# 3-10.net
KiCad netlist of a schematic drawn in Altium Designer
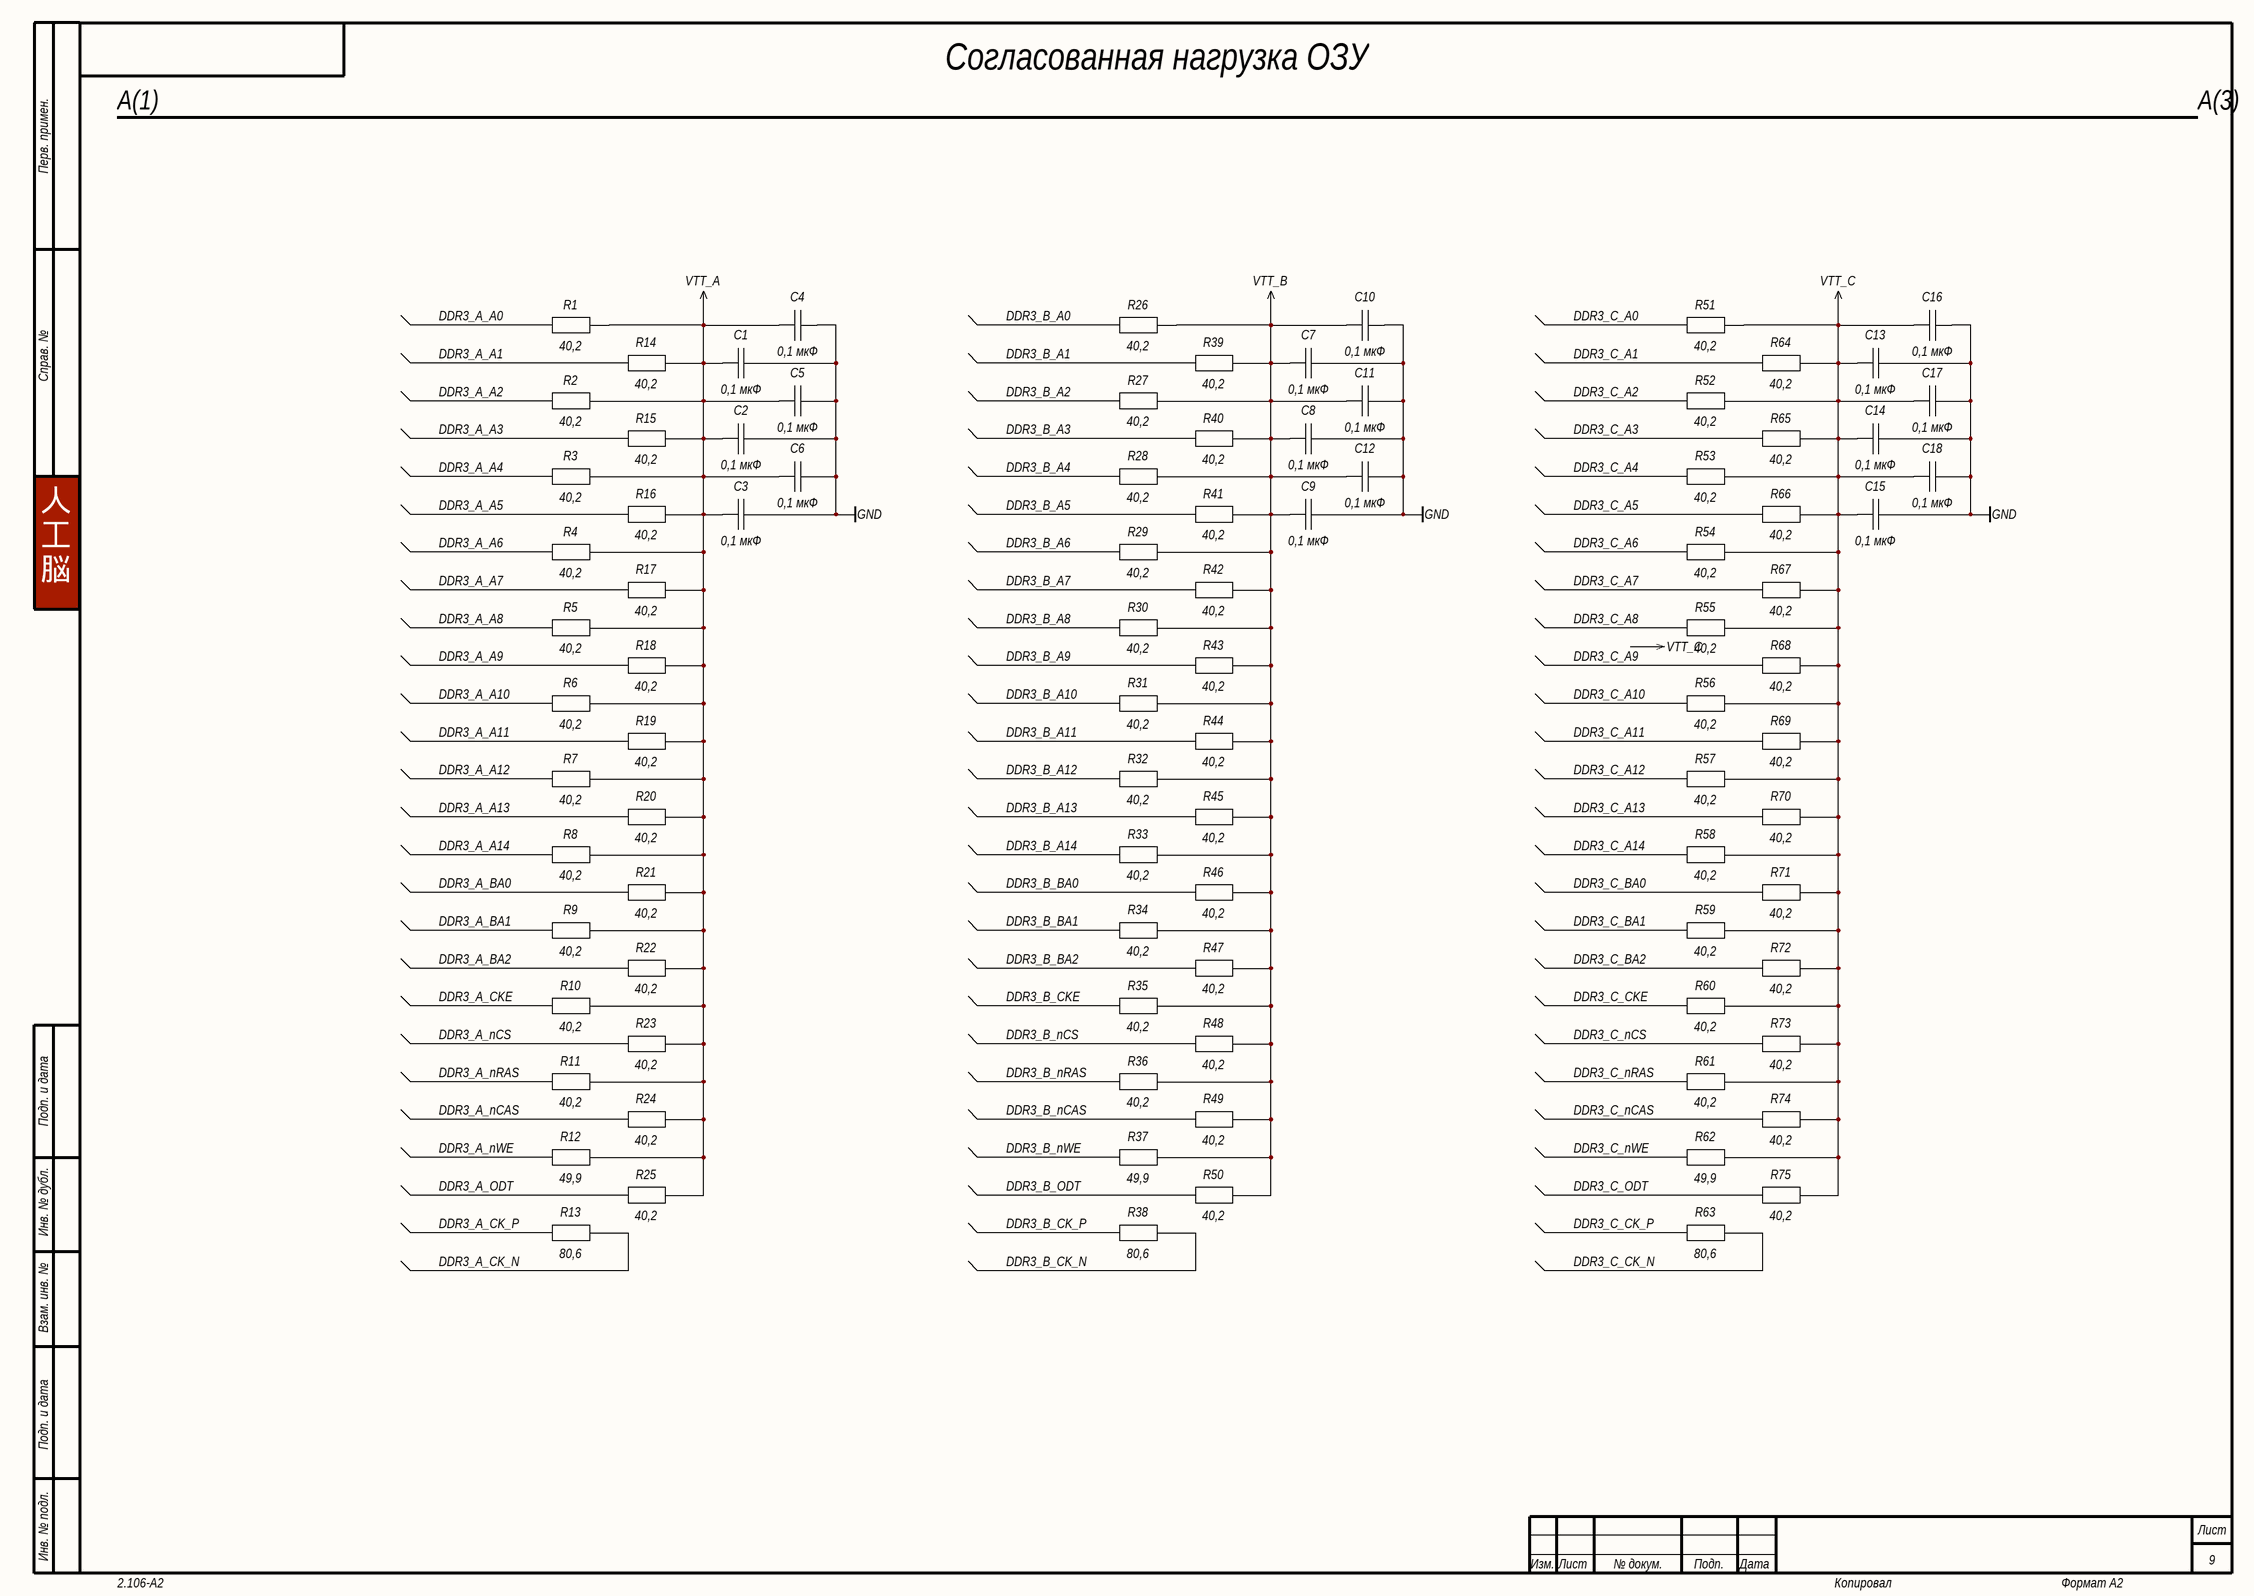
[diagram p0: Э3-10.SchDoc]

(export (version "E")
  (design (tool "Eeschema 10.0.6"))
  (components
    (comp (ref "C1")
      (value "0,1 мкФ")
      (footprint "C0201-B-0.3mm")
      (fields (field (name "Comment") "1"))
      (libsource (lib "Capacitors") (part "Non Polar Hor."))
    )
    (comp (ref "C2")
      (value "0,1 мкФ")
      (footprint "C0201-B-0.3mm")
      (fields (field (name "Comment") "1"))
      (libsource (lib "Capacitors") (part "Non Polar Hor."))
    )
    (comp (ref "C3")
      (value "0,1 мкФ")
      (footprint "C0201-B-0.3mm")
      (fields (field (name "Comment") "1"))
      (libsource (lib "Capacitors") (part "Non Polar Hor."))
    )
    (comp (ref "C4")
      (value "0,1 мкФ")
      (footprint "C0201-B-0.3mm")
      (fields (field (name "Comment") "1"))
      (libsource (lib "Capacitors") (part "Non Polar Hor."))
    )
    (comp (ref "C5")
      (value "0,1 мкФ")
      (footprint "C0201-B-0.3mm")
      (fields (field (name "Comment") "1"))
      (libsource (lib "Capacitors") (part "Non Polar Hor."))
    )
    (comp (ref "C6")
      (value "0,1 мкФ")
      (footprint "C0201-B-0.3mm")
      (fields (field (name "Comment") "1"))
      (libsource (lib "Capacitors") (part "Non Polar Hor."))
    )
    (comp (ref "C7")
      (value "0,1 мкФ")
      (footprint "C0201-B-0.3mm")
      (fields (field (name "Comment") "1"))
      (libsource (lib "Capacitors") (part "Non Polar Hor."))
    )
    (comp (ref "C8")
      (value "0,1 мкФ")
      (footprint "C0201-B-0.3mm")
      (fields (field (name "Comment") "1"))
      (libsource (lib "Capacitors") (part "Non Polar Hor."))
    )
    (comp (ref "C9")
      (value "0,1 мкФ")
      (footprint "C0201-B-0.3mm")
      (fields (field (name "Comment") "1"))
      (libsource (lib "Capacitors") (part "Non Polar Hor."))
    )
    (comp (ref "C10")
      (value "0,1 мкФ")
      (footprint "C0201-B-0.3mm")
      (fields (field (name "Comment") "1"))
      (libsource (lib "Capacitors") (part "Non Polar Hor."))
    )
    (comp (ref "C11")
      (value "0,1 мкФ")
      (footprint "C0201-B-0.3mm")
      (fields (field (name "Comment") "1"))
      (libsource (lib "Capacitors") (part "Non Polar Hor."))
    )
    (comp (ref "C12")
      (value "0,1 мкФ")
      (footprint "C0201-B-0.3mm")
      (fields (field (name "Comment") "1"))
      (libsource (lib "Capacitors") (part "Non Polar Hor."))
    )
    (comp (ref "C13")
      (value "0,1 мкФ")
      (footprint "C0201-B-0.3mm")
      (fields (field (name "Comment") "1"))
      (libsource (lib "Capacitors") (part "Non Polar Hor."))
    )
    (comp (ref "C14")
      (value "0,1 мкФ")
      (footprint "C0201-B-0.3mm")
      (fields (field (name "Comment") "1"))
      (libsource (lib "Capacitors") (part "Non Polar Hor."))
    )
    (comp (ref "C15")
      (value "0,1 мкФ")
      (footprint "C0201-B-0.3mm")
      (fields (field (name "Comment") "1"))
      (libsource (lib "Capacitors") (part "Non Polar Hor."))
    )
    (comp (ref "C16")
      (value "0,1 мкФ")
      (footprint "C0201-B-0.3mm")
      (fields (field (name "Comment") "1"))
      (libsource (lib "Capacitors") (part "Non Polar Hor."))
    )
    (comp (ref "C17")
      (value "0,1 мкФ")
      (footprint "C0201-B-0.3mm")
      (fields (field (name "Comment") "1"))
      (libsource (lib "Capacitors") (part "Non Polar Hor."))
    )
    (comp (ref "C18")
      (value "0,1 мкФ")
      (footprint "C0201-B-0.3mm")
      (fields (field (name "Comment") "1"))
      (libsource (lib "Capacitors") (part "Non Polar Hor."))
    )
    (comp (ref "R1")
      (value "40,2")
      (footprint "CR0201-B-0.25mm")
      (fields (field (name "Comment") "1"))
      (libsource (lib "Resistors") (part "Resistor Hor."))
    )
    (comp (ref "R2")
      (value "40,2")
      (footprint "CR0201-B-0.25mm")
      (fields (field (name "Comment") "1"))
      (libsource (lib "Resistors") (part "Resistor Hor."))
    )
    (comp (ref "R3")
      (value "40,2")
      (footprint "CR0201-B-0.25mm")
      (fields (field (name "Comment") "1"))
      (libsource (lib "Resistors") (part "Resistor Hor."))
    )
    (comp (ref "R4")
      (value "40,2")
      (footprint "CR0201-B-0.25mm")
      (fields (field (name "Comment") "1"))
      (libsource (lib "Resistors") (part "Resistor Hor."))
    )
    (comp (ref "R5")
      (value "40,2")
      (footprint "CR0201-B-0.25mm")
      (fields (field (name "Comment") "1"))
      (libsource (lib "Resistors") (part "Resistor Hor."))
    )
    (comp (ref "R6")
      (value "40,2")
      (footprint "CR0201-B-0.25mm")
      (fields (field (name "Comment") "1"))
      (libsource (lib "Resistors") (part "Resistor Hor."))
    )
    (comp (ref "R7")
      (value "40,2")
      (footprint "CR0201-B-0.25mm")
      (fields (field (name "Comment") "1"))
      (libsource (lib "Resistors") (part "Resistor Hor."))
    )
    (comp (ref "R8")
      (value "40,2")
      (footprint "CR0201-B-0.25mm")
      (fields (field (name "Comment") "1"))
      (libsource (lib "Resistors") (part "Resistor Hor."))
    )
    (comp (ref "R9")
      (value "40,2")
      (footprint "CR0201-B-0.25mm")
      (fields (field (name "Comment") "1"))
      (libsource (lib "Resistors") (part "Resistor Hor."))
    )
    (comp (ref "R10")
      (value "40,2")
      (footprint "CR0201-B-0.25mm")
      (fields (field (name "Comment") "1"))
      (libsource (lib "Resistors") (part "Resistor Hor."))
    )
    (comp (ref "R11")
      (value "40,2")
      (footprint "CR0201-B-0.25mm")
      (fields (field (name "Comment") "1"))
      (libsource (lib "Resistors") (part "Resistor Hor."))
    )
    (comp (ref "R12")
      (value "49,9")
      (footprint "CR0201-B-0.25mm")
      (fields (field (name "Comment") "1"))
      (libsource (lib "Resistors") (part "Resistor Hor."))
    )
    (comp (ref "R13")
      (value "80,6")
      (footprint "CR0201-B-0.25mm")
      (fields (field (name "Comment") "1"))
      (libsource (lib "Resistors") (part "Resistor Hor."))
    )
    (comp (ref "R14")
      (value "40,2")
      (footprint "CR0201-B-0.25mm")
      (fields (field (name "Comment") "1"))
      (libsource (lib "Resistors") (part "Resistor Hor."))
    )
    (comp (ref "R15")
      (value "40,2")
      (footprint "CR0201-B-0.25mm")
      (fields (field (name "Comment") "1"))
      (libsource (lib "Resistors") (part "Resistor Hor."))
    )
    (comp (ref "R16")
      (value "40,2")
      (footprint "CR0201-B-0.25mm")
      (fields (field (name "Comment") "1"))
      (libsource (lib "Resistors") (part "Resistor Hor."))
    )
    (comp (ref "R17")
      (value "40,2")
      (footprint "CR0201-B-0.25mm")
      (fields (field (name "Comment") "1"))
      (libsource (lib "Resistors") (part "Resistor Hor."))
    )
    (comp (ref "R18")
      (value "40,2")
      (footprint "CR0201-B-0.25mm")
      (fields (field (name "Comment") "1"))
      (libsource (lib "Resistors") (part "Resistor Hor."))
    )
    (comp (ref "R19")
      (value "40,2")
      (footprint "CR0201-B-0.25mm")
      (fields (field (name "Comment") "1"))
      (libsource (lib "Resistors") (part "Resistor Hor."))
    )
    (comp (ref "R20")
      (value "40,2")
      (footprint "CR0201-B-0.25mm")
      (fields (field (name "Comment") "1"))
      (libsource (lib "Resistors") (part "Resistor Hor."))
    )
    (comp (ref "R21")
      (value "40,2")
      (footprint "CR0201-B-0.25mm")
      (fields (field (name "Comment") "1"))
      (libsource (lib "Resistors") (part "Resistor Hor."))
    )
    (comp (ref "R22")
      (value "40,2")
      (footprint "CR0201-B-0.25mm")
      (fields (field (name "Comment") "1"))
      (libsource (lib "Resistors") (part "Resistor Hor."))
    )
    (comp (ref "R23")
      (value "40,2")
      (footprint "CR0201-B-0.25mm")
      (fields (field (name "Comment") "1"))
      (libsource (lib "Resistors") (part "Resistor Hor."))
    )
    (comp (ref "R24")
      (value "40,2")
      (footprint "CR0201-B-0.25mm")
      (fields (field (name "Comment") "1"))
      (libsource (lib "Resistors") (part "Resistor Hor."))
    )
    (comp (ref "R25")
      (value "40,2")
      (footprint "CR0201-B-0.25mm")
      (fields (field (name "Comment") "1"))
      (libsource (lib "Resistors") (part "Resistor Hor."))
    )
    (comp (ref "R26")
      (value "40,2")
      (footprint "CR0201-B-0.25mm")
      (fields (field (name "Comment") "1"))
      (libsource (lib "Resistors") (part "Resistor Hor."))
    )
    (comp (ref "R27")
      (value "40,2")
      (footprint "CR0201-B-0.25mm")
      (fields (field (name "Comment") "1"))
      (libsource (lib "Resistors") (part "Resistor Hor."))
    )
    (comp (ref "R28")
      (value "40,2")
      (footprint "CR0201-B-0.25mm")
      (fields (field (name "Comment") "1"))
      (libsource (lib "Resistors") (part "Resistor Hor."))
    )
    (comp (ref "R29")
      (value "40,2")
      (footprint "CR0201-B-0.25mm")
      (fields (field (name "Comment") "1"))
      (libsource (lib "Resistors") (part "Resistor Hor."))
    )
    (comp (ref "R30")
      (value "40,2")
      (footprint "CR0201-B-0.25mm")
      (fields (field (name "Comment") "1"))
      (libsource (lib "Resistors") (part "Resistor Hor."))
    )
    (comp (ref "R31")
      (value "40,2")
      (footprint "CR0201-B-0.25mm")
      (fields (field (name "Comment") "1"))
      (libsource (lib "Resistors") (part "Resistor Hor."))
    )
    (comp (ref "R32")
      (value "40,2")
      (footprint "CR0201-B-0.25mm")
      (fields (field (name "Comment") "1"))
      (libsource (lib "Resistors") (part "Resistor Hor."))
    )
    (comp (ref "R33")
      (value "40,2")
      (footprint "CR0201-B-0.25mm")
      (fields (field (name "Comment") "1"))
      (libsource (lib "Resistors") (part "Resistor Hor."))
    )
    (comp (ref "R34")
      (value "40,2")
      (footprint "CR0201-B-0.25mm")
      (fields (field (name "Comment") "1"))
      (libsource (lib "Resistors") (part "Resistor Hor."))
    )
    (comp (ref "R35")
      (value "40,2")
      (footprint "CR0201-B-0.25mm")
      (fields (field (name "Comment") "1"))
      (libsource (lib "Resistors") (part "Resistor Hor."))
    )
    (comp (ref "R36")
      (value "40,2")
      (footprint "CR0201-B-0.25mm")
      (fields (field (name "Comment") "1"))
      (libsource (lib "Resistors") (part "Resistor Hor."))
    )
    (comp (ref "R37")
      (value "49,9")
      (footprint "CR0201-B-0.25mm")
      (fields (field (name "Comment") "1"))
      (libsource (lib "Resistors") (part "Resistor Hor."))
    )
    (comp (ref "R38")
      (value "80,6")
      (footprint "CR0201-B-0.25mm")
      (fields (field (name "Comment") "1"))
      (libsource (lib "Resistors") (part "Resistor Hor."))
    )
    (comp (ref "R39")
      (value "40,2")
      (footprint "CR0201-B-0.25mm")
      (fields (field (name "Comment") "1"))
      (libsource (lib "Resistors") (part "Resistor Hor."))
    )
    (comp (ref "R40")
      (value "40,2")
      (footprint "CR0201-B-0.25mm")
      (fields (field (name "Comment") "1"))
      (libsource (lib "Resistors") (part "Resistor Hor."))
    )
    (comp (ref "R41")
      (value "40,2")
      (footprint "CR0201-B-0.25mm")
      (fields (field (name "Comment") "1"))
      (libsource (lib "Resistors") (part "Resistor Hor."))
    )
    (comp (ref "R42")
      (value "40,2")
      (footprint "CR0201-B-0.25mm")
      (fields (field (name "Comment") "1"))
      (libsource (lib "Resistors") (part "Resistor Hor."))
    )
    (comp (ref "R43")
      (value "40,2")
      (footprint "CR0201-B-0.25mm")
      (fields (field (name "Comment") "1"))
      (libsource (lib "Resistors") (part "Resistor Hor."))
    )
    (comp (ref "R44")
      (value "40,2")
      (footprint "CR0201-B-0.25mm")
      (fields (field (name "Comment") "1"))
      (libsource (lib "Resistors") (part "Resistor Hor."))
    )
    (comp (ref "R45")
      (value "40,2")
      (footprint "CR0201-B-0.25mm")
      (fields (field (name "Comment") "1"))
      (libsource (lib "Resistors") (part "Resistor Hor."))
    )
    (comp (ref "R46")
      (value "40,2")
      (footprint "CR0201-B-0.25mm")
      (fields (field (name "Comment") "1"))
      (libsource (lib "Resistors") (part "Resistor Hor."))
    )
    (comp (ref "R47")
      (value "40,2")
      (footprint "CR0201-B-0.25mm")
      (fields (field (name "Comment") "1"))
      (libsource (lib "Resistors") (part "Resistor Hor."))
    )
    (comp (ref "R48")
      (value "40,2")
      (footprint "CR0201-B-0.25mm")
      (fields (field (name "Comment") "1"))
      (libsource (lib "Resistors") (part "Resistor Hor."))
    )
    (comp (ref "R49")
      (value "40,2")
      (footprint "CR0201-B-0.25mm")
      (fields (field (name "Comment") "1"))
      (libsource (lib "Resistors") (part "Resistor Hor."))
    )
    (comp (ref "R50")
      (value "40,2")
      (footprint "CR0201-B-0.25mm")
      (fields (field (name "Comment") "1"))
      (libsource (lib "Resistors") (part "Resistor Hor."))
    )
    (comp (ref "R51")
      (value "40,2")
      (footprint "CR0201-B-0.25mm")
      (fields (field (name "Comment") "1"))
      (libsource (lib "Resistors") (part "Resistor Hor."))
    )
    (comp (ref "R52")
      (value "40,2")
      (footprint "CR0201-B-0.25mm")
      (fields (field (name "Comment") "1"))
      (libsource (lib "Resistors") (part "Resistor Hor."))
    )
    (comp (ref "R53")
      (value "40,2")
      (footprint "CR0201-B-0.25mm")
      (fields (field (name "Comment") "1"))
      (libsource (lib "Resistors") (part "Resistor Hor."))
    )
    (comp (ref "R54")
      (value "40,2")
      (footprint "CR0201-B-0.25mm")
      (fields (field (name "Comment") "1"))
      (libsource (lib "Resistors") (part "Resistor Hor."))
    )
    (comp (ref "R55")
      (value "40,2")
      (footprint "CR0201-B-0.25mm")
      (fields (field (name "Comment") "1"))
      (libsource (lib "Resistors") (part "Resistor Hor."))
    )
    (comp (ref "R56")
      (value "40,2")
      (footprint "CR0201-B-0.25mm")
      (fields (field (name "Comment") "1"))
      (libsource (lib "Resistors") (part "Resistor Hor."))
    )
    (comp (ref "R57")
      (value "40,2")
      (footprint "CR0201-B-0.25mm")
      (fields (field (name "Comment") "1"))
      (libsource (lib "Resistors") (part "Resistor Hor."))
    )
    (comp (ref "R58")
      (value "40,2")
      (footprint "CR0201-B-0.25mm")
      (fields (field (name "Comment") "1"))
      (libsource (lib "Resistors") (part "Resistor Hor."))
    )
    (comp (ref "R59")
      (value "40,2")
      (footprint "CR0201-B-0.25mm")
      (fields (field (name "Comment") "1"))
      (libsource (lib "Resistors") (part "Resistor Hor."))
    )
    (comp (ref "R60")
      (value "40,2")
      (footprint "CR0201-B-0.25mm")
      (fields (field (name "Comment") "1"))
      (libsource (lib "Resistors") (part "Resistor Hor."))
    )
    (comp (ref "R61")
      (value "40,2")
      (footprint "CR0201-B-0.25mm")
      (fields (field (name "Comment") "1"))
      (libsource (lib "Resistors") (part "Resistor Hor."))
    )
    (comp (ref "R62")
      (value "49,9")
      (footprint "CR0201-B-0.25mm")
      (fields (field (name "Comment") "1"))
      (libsource (lib "Resistors") (part "Resistor Hor."))
    )
    (comp (ref "R63")
      (value "80,6")
      (footprint "CR0201-B-0.25mm")
      (fields (field (name "Comment") "1"))
      (libsource (lib "Resistors") (part "Resistor Hor."))
    )
    (comp (ref "R64")
      (value "40,2")
      (footprint "CR0201-B-0.25mm")
      (fields (field (name "Comment") "1"))
      (libsource (lib "Resistors") (part "Resistor Hor."))
    )
    (comp (ref "R65")
      (value "40,2")
      (footprint "CR0201-B-0.25mm")
      (fields (field (name "Comment") "1"))
      (libsource (lib "Resistors") (part "Resistor Hor."))
    )
    (comp (ref "R66")
      (value "40,2")
      (footprint "CR0201-B-0.25mm")
      (fields (field (name "Comment") "1"))
      (libsource (lib "Resistors") (part "Resistor Hor."))
    )
    (comp (ref "R67")
      (value "40,2")
      (footprint "CR0201-B-0.25mm")
      (fields (field (name "Comment") "1"))
      (libsource (lib "Resistors") (part "Resistor Hor."))
    )
    (comp (ref "R68")
      (value "40,2")
      (footprint "CR0201-B-0.25mm")
      (fields (field (name "Comment") "1"))
      (libsource (lib "Resistors") (part "Resistor Hor."))
    )
    (comp (ref "R69")
      (value "40,2")
      (footprint "CR0201-B-0.25mm")
      (fields (field (name "Comment") "1"))
      (libsource (lib "Resistors") (part "Resistor Hor."))
    )
    (comp (ref "R70")
      (value "40,2")
      (footprint "CR0201-B-0.25mm")
      (fields (field (name "Comment") "1"))
      (libsource (lib "Resistors") (part "Resistor Hor."))
    )
    (comp (ref "R71")
      (value "40,2")
      (footprint "CR0201-B-0.25mm")
      (fields (field (name "Comment") "1"))
      (libsource (lib "Resistors") (part "Resistor Hor."))
    )
    (comp (ref "R72")
      (value "40,2")
      (footprint "CR0201-B-0.25mm")
      (fields (field (name "Comment") "1"))
      (libsource (lib "Resistors") (part "Resistor Hor."))
    )
    (comp (ref "R73")
      (value "40,2")
      (footprint "CR0201-B-0.25mm")
      (fields (field (name "Comment") "1"))
      (libsource (lib "Resistors") (part "Resistor Hor."))
    )
    (comp (ref "R74")
      (value "40,2")
      (footprint "CR0201-B-0.25mm")
      (fields (field (name "Comment") "1"))
      (libsource (lib "Resistors") (part "Resistor Hor."))
    )
    (comp (ref "R75")
      (value "40,2")
      (footprint "CR0201-B-0.25mm")
      (fields (field (name "Comment") "1"))
      (libsource (lib "Resistors") (part "Resistor Hor."))
    )
  )
  (nets
    (net (code "1") (name "/DDR3_A_A0") (class "Default")
      (node (ref "R1") (pin "1") (pinfunction "1_1") (pintype "passive"))
    )
    (net (code "2") (name "/DDR3_A_A1") (class "Default")
      (node (ref "R14") (pin "1") (pinfunction "1_1") (pintype "passive"))
    )
    (net (code "3") (name "/DDR3_A_A2") (class "Default")
      (node (ref "R2") (pin "1") (pinfunction "1_1") (pintype "passive"))
    )
    (net (code "4") (name "/DDR3_A_A3") (class "Default")
      (node (ref "R15") (pin "1") (pinfunction "1_1") (pintype "passive"))
    )
    (net (code "5") (name "/DDR3_A_A4") (class "Default")
      (node (ref "R3") (pin "1") (pinfunction "1_1") (pintype "passive"))
    )
    (net (code "6") (name "/DDR3_A_A5") (class "Default")
      (node (ref "R16") (pin "1") (pinfunction "1_1") (pintype "passive"))
    )
    (net (code "7") (name "/DDR3_A_A6") (class "Default")
      (node (ref "R4") (pin "1") (pinfunction "1_1") (pintype "passive"))
    )
    (net (code "8") (name "/DDR3_A_A7") (class "Default")
      (node (ref "R17") (pin "1") (pinfunction "1_1") (pintype "passive"))
    )
    (net (code "9") (name "/DDR3_A_A8") (class "Default")
      (node (ref "R5") (pin "1") (pinfunction "1_1") (pintype "passive"))
    )
    (net (code "10") (name "/DDR3_A_A9") (class "Default")
      (node (ref "R18") (pin "1") (pinfunction "1_1") (pintype "passive"))
    )
    (net (code "11") (name "/DDR3_A_A10") (class "Default")
      (node (ref "R6") (pin "1") (pinfunction "1_1") (pintype "passive"))
    )
    (net (code "12") (name "/DDR3_A_A11") (class "Default")
      (node (ref "R19") (pin "1") (pinfunction "1_1") (pintype "passive"))
    )
    (net (code "13") (name "/DDR3_A_A12") (class "Default")
      (node (ref "R7") (pin "1") (pinfunction "1_1") (pintype "passive"))
    )
    (net (code "14") (name "/DDR3_A_A13") (class "Default")
      (node (ref "R20") (pin "1") (pinfunction "1_1") (pintype "passive"))
    )
    (net (code "15") (name "/DDR3_A_A14") (class "Default")
      (node (ref "R8") (pin "1") (pinfunction "1_1") (pintype "passive"))
    )
    (net (code "16") (name "/DDR3_A_BA0") (class "Default")
      (node (ref "R21") (pin "1") (pinfunction "1_1") (pintype "passive"))
    )
    (net (code "17") (name "/DDR3_A_BA1") (class "Default")
      (node (ref "R9") (pin "1") (pinfunction "1_1") (pintype "passive"))
    )
    (net (code "18") (name "/DDR3_A_BA2") (class "Default")
      (node (ref "R22") (pin "1") (pinfunction "1_1") (pintype "passive"))
    )
    (net (code "19") (name "/DDR3_A_CKE") (class "Default")
      (node (ref "R10") (pin "1") (pinfunction "1_1") (pintype "passive"))
    )
    (net (code "20") (name "/DDR3_A_CK_N") (class "Default")
      (node (ref "R13") (pin "2") (pinfunction "2_2") (pintype "passive"))
    )
    (net (code "21") (name "/DDR3_A_CK_P") (class "Default")
      (node (ref "R13") (pin "1") (pinfunction "1_1") (pintype "passive"))
    )
    (net (code "22") (name "/DDR3_A_ODT") (class "Default")
      (node (ref "R25") (pin "1") (pinfunction "1_1") (pintype "passive"))
    )
    (net (code "23") (name "/DDR3_A_nCAS") (class "Default")
      (node (ref "R24") (pin "1") (pinfunction "1_1") (pintype "passive"))
    )
    (net (code "24") (name "/DDR3_A_nCS") (class "Default")
      (node (ref "R23") (pin "1") (pinfunction "1_1") (pintype "passive"))
    )
    (net (code "25") (name "/DDR3_A_nRAS") (class "Default")
      (node (ref "R11") (pin "1") (pinfunction "1_1") (pintype "passive"))
    )
    (net (code "26") (name "/DDR3_A_nWE") (class "Default")
      (node (ref "R12") (pin "1") (pinfunction "1_1") (pintype "passive"))
    )
    (net (code "27") (name "/DDR3_B_A0") (class "Default")
      (node (ref "R26") (pin "1") (pinfunction "1_1") (pintype "passive"))
    )
    (net (code "28") (name "/DDR3_B_A1") (class "Default")
      (node (ref "R39") (pin "1") (pinfunction "1_1") (pintype "passive"))
    )
    (net (code "29") (name "/DDR3_B_A2") (class "Default")
      (node (ref "R27") (pin "1") (pinfunction "1_1") (pintype "passive"))
    )
    (net (code "30") (name "/DDR3_B_A3") (class "Default")
      (node (ref "R40") (pin "1") (pinfunction "1_1") (pintype "passive"))
    )
    (net (code "31") (name "/DDR3_B_A4") (class "Default")
      (node (ref "R28") (pin "1") (pinfunction "1_1") (pintype "passive"))
    )
    (net (code "32") (name "/DDR3_B_A5") (class "Default")
      (node (ref "R41") (pin "1") (pinfunction "1_1") (pintype "passive"))
    )
    (net (code "33") (name "/DDR3_B_A6") (class "Default")
      (node (ref "R29") (pin "1") (pinfunction "1_1") (pintype "passive"))
    )
    (net (code "34") (name "/DDR3_B_A7") (class "Default")
      (node (ref "R42") (pin "1") (pinfunction "1_1") (pintype "passive"))
    )
    (net (code "35") (name "/DDR3_B_A8") (class "Default")
      (node (ref "R30") (pin "1") (pinfunction "1_1") (pintype "passive"))
    )
    (net (code "36") (name "/DDR3_B_A9") (class "Default")
      (node (ref "R43") (pin "1") (pinfunction "1_1") (pintype "passive"))
    )
    (net (code "37") (name "/DDR3_B_A10") (class "Default")
      (node (ref "R31") (pin "1") (pinfunction "1_1") (pintype "passive"))
    )
    (net (code "38") (name "/DDR3_B_A11") (class "Default")
      (node (ref "R44") (pin "1") (pinfunction "1_1") (pintype "passive"))
    )
    (net (code "39") (name "/DDR3_B_A12") (class "Default")
      (node (ref "R32") (pin "1") (pinfunction "1_1") (pintype "passive"))
    )
    (net (code "40") (name "/DDR3_B_A13") (class "Default")
      (node (ref "R45") (pin "1") (pinfunction "1_1") (pintype "passive"))
    )
    (net (code "41") (name "/DDR3_B_A14") (class "Default")
      (node (ref "R33") (pin "1") (pinfunction "1_1") (pintype "passive"))
    )
    (net (code "42") (name "/DDR3_B_BA0") (class "Default")
      (node (ref "R46") (pin "1") (pinfunction "1_1") (pintype "passive"))
    )
    (net (code "43") (name "/DDR3_B_BA1") (class "Default")
      (node (ref "R34") (pin "1") (pinfunction "1_1") (pintype "passive"))
    )
    (net (code "44") (name "/DDR3_B_BA2") (class "Default")
      (node (ref "R47") (pin "1") (pinfunction "1_1") (pintype "passive"))
    )
    (net (code "45") (name "/DDR3_B_CKE") (class "Default")
      (node (ref "R35") (pin "1") (pinfunction "1_1") (pintype "passive"))
    )
    (net (code "46") (name "/DDR3_B_CK_N") (class "Default")
      (node (ref "R38") (pin "2") (pinfunction "2_2") (pintype "passive"))
    )
    (net (code "47") (name "/DDR3_B_CK_P") (class "Default")
      (node (ref "R38") (pin "1") (pinfunction "1_1") (pintype "passive"))
    )
    (net (code "48") (name "/DDR3_B_ODT") (class "Default")
      (node (ref "R50") (pin "1") (pinfunction "1_1") (pintype "passive"))
    )
    (net (code "49") (name "/DDR3_B_nCAS") (class "Default")
      (node (ref "R49") (pin "1") (pinfunction "1_1") (pintype "passive"))
    )
    (net (code "50") (name "/DDR3_B_nCS") (class "Default")
      (node (ref "R48") (pin "1") (pinfunction "1_1") (pintype "passive"))
    )
    (net (code "51") (name "/DDR3_B_nRAS") (class "Default")
      (node (ref "R36") (pin "1") (pinfunction "1_1") (pintype "passive"))
    )
    (net (code "52") (name "/DDR3_B_nWE") (class "Default")
      (node (ref "R37") (pin "1") (pinfunction "1_1") (pintype "passive"))
    )
    (net (code "53") (name "/DDR3_C_A0") (class "Default")
      (node (ref "R51") (pin "1") (pinfunction "1_1") (pintype "passive"))
    )
    (net (code "54") (name "/DDR3_C_A1") (class "Default")
      (node (ref "R64") (pin "1") (pinfunction "1_1") (pintype "passive"))
    )
    (net (code "55") (name "/DDR3_C_A2") (class "Default")
      (node (ref "R52") (pin "1") (pinfunction "1_1") (pintype "passive"))
    )
    (net (code "56") (name "/DDR3_C_A3") (class "Default")
      (node (ref "R65") (pin "1") (pinfunction "1_1") (pintype "passive"))
    )
    (net (code "57") (name "/DDR3_C_A4") (class "Default")
      (node (ref "R53") (pin "1") (pinfunction "1_1") (pintype "passive"))
    )
    (net (code "58") (name "/DDR3_C_A5") (class "Default")
      (node (ref "R66") (pin "1") (pinfunction "1_1") (pintype "passive"))
    )
    (net (code "59") (name "/DDR3_C_A6") (class "Default")
      (node (ref "R54") (pin "1") (pinfunction "1_1") (pintype "passive"))
    )
    (net (code "60") (name "/DDR3_C_A7") (class "Default")
      (node (ref "R67") (pin "1") (pinfunction "1_1") (pintype "passive"))
    )
    (net (code "61") (name "/DDR3_C_A8") (class "Default")
      (node (ref "R55") (pin "1") (pinfunction "1_1") (pintype "passive"))
    )
    (net (code "62") (name "/DDR3_C_A9") (class "Default")
      (node (ref "R68") (pin "1") (pinfunction "1_1") (pintype "passive"))
    )
    (net (code "63") (name "/DDR3_C_A10") (class "Default")
      (node (ref "R56") (pin "1") (pinfunction "1_1") (pintype "passive"))
    )
    (net (code "64") (name "/DDR3_C_A11") (class "Default")
      (node (ref "R69") (pin "1") (pinfunction "1_1") (pintype "passive"))
    )
    (net (code "65") (name "/DDR3_C_A12") (class "Default")
      (node (ref "R57") (pin "1") (pinfunction "1_1") (pintype "passive"))
    )
    (net (code "66") (name "/DDR3_C_A13") (class "Default")
      (node (ref "R70") (pin "1") (pinfunction "1_1") (pintype "passive"))
    )
    (net (code "67") (name "/DDR3_C_A14") (class "Default")
      (node (ref "R58") (pin "1") (pinfunction "1_1") (pintype "passive"))
    )
    (net (code "68") (name "/DDR3_C_BA0") (class "Default")
      (node (ref "R71") (pin "1") (pinfunction "1_1") (pintype "passive"))
    )
    (net (code "69") (name "/DDR3_C_BA1") (class "Default")
      (node (ref "R59") (pin "1") (pinfunction "1_1") (pintype "passive"))
    )
    (net (code "70") (name "/DDR3_C_BA2") (class "Default")
      (node (ref "R72") (pin "1") (pinfunction "1_1") (pintype "passive"))
    )
    (net (code "71") (name "/DDR3_C_CKE") (class "Default")
      (node (ref "R60") (pin "1") (pinfunction "1_1") (pintype "passive"))
    )
    (net (code "72") (name "/DDR3_C_CK_N") (class "Default")
      (node (ref "R63") (pin "2") (pinfunction "2_2") (pintype "passive"))
    )
    (net (code "73") (name "/DDR3_C_CK_P") (class "Default")
      (node (ref "R63") (pin "1") (pinfunction "1_1") (pintype "passive"))
    )
    (net (code "74") (name "/DDR3_C_ODT") (class "Default")
      (node (ref "R75") (pin "1") (pinfunction "1_1") (pintype "passive"))
    )
    (net (code "75") (name "/DDR3_C_nCAS") (class "Default")
      (node (ref "R74") (pin "1") (pinfunction "1_1") (pintype "passive"))
    )
    (net (code "76") (name "/DDR3_C_nCS") (class "Default")
      (node (ref "R73") (pin "1") (pinfunction "1_1") (pintype "passive"))
    )
    (net (code "77") (name "/DDR3_C_nRAS") (class "Default")
      (node (ref "R61") (pin "1") (pinfunction "1_1") (pintype "passive"))
    )
    (net (code "78") (name "/DDR3_C_nWE") (class "Default")
      (node (ref "R62") (pin "1") (pinfunction "1_1") (pintype "passive"))
    )
    (net (code "79") (name "GND") (class "Default")
      (node (ref "C1") (pin "2") (pinfunction "2_2") (pintype "passive"))
      (node (ref "C10") (pin "2") (pinfunction "2_2") (pintype "passive"))
      (node (ref "C11") (pin "2") (pinfunction "2_2") (pintype "passive"))
      (node (ref "C12") (pin "2") (pinfunction "2_2") (pintype "passive"))
      (node (ref "C13") (pin "2") (pinfunction "2_2") (pintype "passive"))
      (node (ref "C14") (pin "2") (pinfunction "2_2") (pintype "passive"))
      (node (ref "C15") (pin "2") (pinfunction "2_2") (pintype "passive"))
      (node (ref "C16") (pin "2") (pinfunction "2_2") (pintype "passive"))
      (node (ref "C17") (pin "2") (pinfunction "2_2") (pintype "passive"))
      (node (ref "C18") (pin "2") (pinfunction "2_2") (pintype "passive"))
      (node (ref "C2") (pin "2") (pinfunction "2_2") (pintype "passive"))
      (node (ref "C3") (pin "2") (pinfunction "2_2") (pintype "passive"))
      (node (ref "C4") (pin "2") (pinfunction "2_2") (pintype "passive"))
      (node (ref "C5") (pin "2") (pinfunction "2_2") (pintype "passive"))
      (node (ref "C6") (pin "2") (pinfunction "2_2") (pintype "passive"))
      (node (ref "C7") (pin "2") (pinfunction "2_2") (pintype "passive"))
      (node (ref "C8") (pin "2") (pinfunction "2_2") (pintype "passive"))
      (node (ref "C9") (pin "2") (pinfunction "2_2") (pintype "passive"))
    )
    (net (code "80") (name "VTT_A") (class "Default")
      (node (ref "C1") (pin "1") (pinfunction "1_1") (pintype "passive"))
      (node (ref "C2") (pin "1") (pinfunction "1_1") (pintype "passive"))
      (node (ref "C3") (pin "1") (pinfunction "1_1") (pintype "passive"))
      (node (ref "C4") (pin "1") (pinfunction "1_1") (pintype "passive"))
      (node (ref "C5") (pin "1") (pinfunction "1_1") (pintype "passive"))
      (node (ref "C6") (pin "1") (pinfunction "1_1") (pintype "passive"))
      (node (ref "R1") (pin "2") (pinfunction "2_2") (pintype "passive"))
      (node (ref "R10") (pin "2") (pinfunction "2_2") (pintype "passive"))
      (node (ref "R11") (pin "2") (pinfunction "2_2") (pintype "passive"))
      (node (ref "R12") (pin "2") (pinfunction "2_2") (pintype "passive"))
      (node (ref "R14") (pin "2") (pinfunction "2_2") (pintype "passive"))
      (node (ref "R15") (pin "2") (pinfunction "2_2") (pintype "passive"))
      (node (ref "R16") (pin "2") (pinfunction "2_2") (pintype "passive"))
      (node (ref "R17") (pin "2") (pinfunction "2_2") (pintype "passive"))
      (node (ref "R18") (pin "2") (pinfunction "2_2") (pintype "passive"))
      (node (ref "R19") (pin "2") (pinfunction "2_2") (pintype "passive"))
      (node (ref "R2") (pin "2") (pinfunction "2_2") (pintype "passive"))
      (node (ref "R20") (pin "2") (pinfunction "2_2") (pintype "passive"))
      (node (ref "R21") (pin "2") (pinfunction "2_2") (pintype "passive"))
      (node (ref "R22") (pin "2") (pinfunction "2_2") (pintype "passive"))
      (node (ref "R23") (pin "2") (pinfunction "2_2") (pintype "passive"))
      (node (ref "R24") (pin "2") (pinfunction "2_2") (pintype "passive"))
      (node (ref "R25") (pin "2") (pinfunction "2_2") (pintype "passive"))
      (node (ref "R3") (pin "2") (pinfunction "2_2") (pintype "passive"))
      (node (ref "R4") (pin "2") (pinfunction "2_2") (pintype "passive"))
      (node (ref "R5") (pin "2") (pinfunction "2_2") (pintype "passive"))
      (node (ref "R6") (pin "2") (pinfunction "2_2") (pintype "passive"))
      (node (ref "R7") (pin "2") (pinfunction "2_2") (pintype "passive"))
      (node (ref "R8") (pin "2") (pinfunction "2_2") (pintype "passive"))
      (node (ref "R9") (pin "2") (pinfunction "2_2") (pintype "passive"))
    )
    (net (code "81") (name "VTT_B") (class "Default")
      (node (ref "C10") (pin "1") (pinfunction "1_1") (pintype "passive"))
      (node (ref "C11") (pin "1") (pinfunction "1_1") (pintype "passive"))
      (node (ref "C12") (pin "1") (pinfunction "1_1") (pintype "passive"))
      (node (ref "C7") (pin "1") (pinfunction "1_1") (pintype "passive"))
      (node (ref "C8") (pin "1") (pinfunction "1_1") (pintype "passive"))
      (node (ref "C9") (pin "1") (pinfunction "1_1") (pintype "passive"))
      (node (ref "R26") (pin "2") (pinfunction "2_2") (pintype "passive"))
      (node (ref "R27") (pin "2") (pinfunction "2_2") (pintype "passive"))
      (node (ref "R28") (pin "2") (pinfunction "2_2") (pintype "passive"))
      (node (ref "R29") (pin "2") (pinfunction "2_2") (pintype "passive"))
      (node (ref "R30") (pin "2") (pinfunction "2_2") (pintype "passive"))
      (node (ref "R31") (pin "2") (pinfunction "2_2") (pintype "passive"))
      (node (ref "R32") (pin "2") (pinfunction "2_2") (pintype "passive"))
      (node (ref "R33") (pin "2") (pinfunction "2_2") (pintype "passive"))
      (node (ref "R34") (pin "2") (pinfunction "2_2") (pintype "passive"))
      (node (ref "R35") (pin "2") (pinfunction "2_2") (pintype "passive"))
      (node (ref "R36") (pin "2") (pinfunction "2_2") (pintype "passive"))
      (node (ref "R37") (pin "2") (pinfunction "2_2") (pintype "passive"))
      (node (ref "R39") (pin "2") (pinfunction "2_2") (pintype "passive"))
      (node (ref "R40") (pin "2") (pinfunction "2_2") (pintype "passive"))
      (node (ref "R41") (pin "2") (pinfunction "2_2") (pintype "passive"))
      (node (ref "R42") (pin "2") (pinfunction "2_2") (pintype "passive"))
      (node (ref "R43") (pin "2") (pinfunction "2_2") (pintype "passive"))
      (node (ref "R44") (pin "2") (pinfunction "2_2") (pintype "passive"))
      (node (ref "R45") (pin "2") (pinfunction "2_2") (pintype "passive"))
      (node (ref "R46") (pin "2") (pinfunction "2_2") (pintype "passive"))
      (node (ref "R47") (pin "2") (pinfunction "2_2") (pintype "passive"))
      (node (ref "R48") (pin "2") (pinfunction "2_2") (pintype "passive"))
      (node (ref "R49") (pin "2") (pinfunction "2_2") (pintype "passive"))
      (node (ref "R50") (pin "2") (pinfunction "2_2") (pintype "passive"))
    )
    (net (code "82") (name "VTT_C") (class "Default")
      (node (ref "C13") (pin "1") (pinfunction "1_1") (pintype "passive"))
      (node (ref "C14") (pin "1") (pinfunction "1_1") (pintype "passive"))
      (node (ref "C15") (pin "1") (pinfunction "1_1") (pintype "passive"))
      (node (ref "C16") (pin "1") (pinfunction "1_1") (pintype "passive"))
      (node (ref "C17") (pin "1") (pinfunction "1_1") (pintype "passive"))
      (node (ref "C18") (pin "1") (pinfunction "1_1") (pintype "passive"))
      (node (ref "R51") (pin "2") (pinfunction "2_2") (pintype "passive"))
      (node (ref "R52") (pin "2") (pinfunction "2_2") (pintype "passive"))
      (node (ref "R53") (pin "2") (pinfunction "2_2") (pintype "passive"))
      (node (ref "R54") (pin "2") (pinfunction "2_2") (pintype "passive"))
      (node (ref "R55") (pin "2") (pinfunction "2_2") (pintype "passive"))
      (node (ref "R56") (pin "2") (pinfunction "2_2") (pintype "passive"))
      (node (ref "R57") (pin "2") (pinfunction "2_2") (pintype "passive"))
      (node (ref "R58") (pin "2") (pinfunction "2_2") (pintype "passive"))
      (node (ref "R59") (pin "2") (pinfunction "2_2") (pintype "passive"))
      (node (ref "R60") (pin "2") (pinfunction "2_2") (pintype "passive"))
      (node (ref "R61") (pin "2") (pinfunction "2_2") (pintype "passive"))
      (node (ref "R62") (pin "2") (pinfunction "2_2") (pintype "passive"))
      (node (ref "R64") (pin "2") (pinfunction "2_2") (pintype "passive"))
      (node (ref "R65") (pin "2") (pinfunction "2_2") (pintype "passive"))
      (node (ref "R66") (pin "2") (pinfunction "2_2") (pintype "passive"))
      (node (ref "R67") (pin "2") (pinfunction "2_2") (pintype "passive"))
      (node (ref "R68") (pin "2") (pinfunction "2_2") (pintype "passive"))
      (node (ref "R69") (pin "2") (pinfunction "2_2") (pintype "passive"))
      (node (ref "R70") (pin "2") (pinfunction "2_2") (pintype "passive"))
      (node (ref "R71") (pin "2") (pinfunction "2_2") (pintype "passive"))
      (node (ref "R72") (pin "2") (pinfunction "2_2") (pintype "passive"))
      (node (ref "R73") (pin "2") (pinfunction "2_2") (pintype "passive"))
      (node (ref "R74") (pin "2") (pinfunction "2_2") (pintype "passive"))
      (node (ref "R75") (pin "2") (pinfunction "2_2") (pintype "passive"))
    )
  )
)
